# receiver.net
KiCad netlist of a schematic drawn in EAGLE
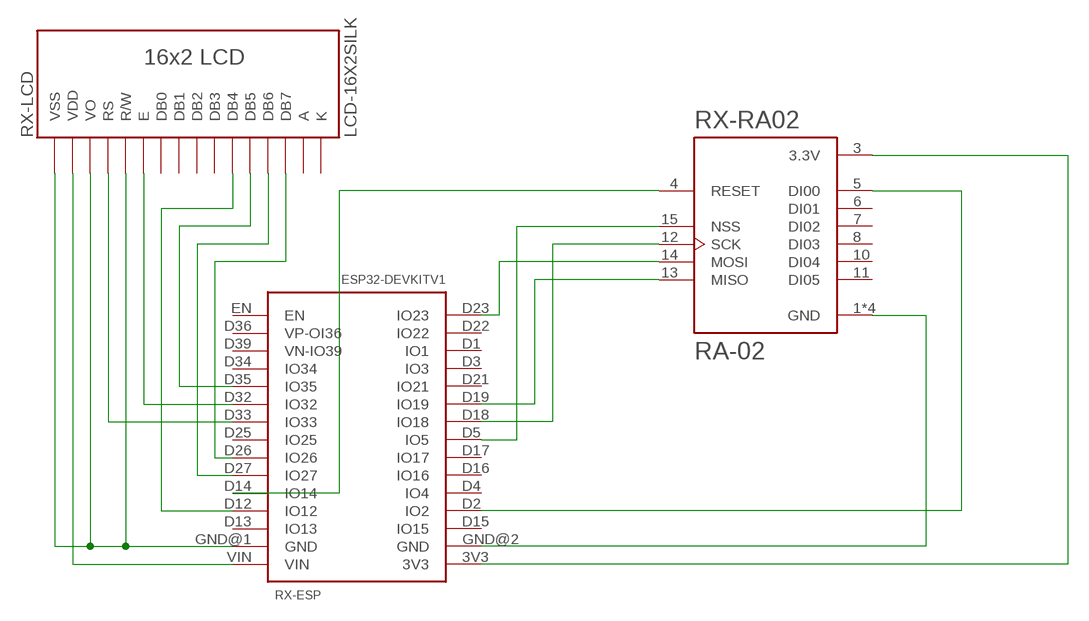
[diagram p0: schematic, sheet 1]

(export (version "E")
  (design (tool "Eeschema 10.0.6"))
  (components
    (comp (ref "RX-ESP")
      (value "ESP32DEVKITV1")
      (footprint "eagle-import:ESP32-DEVKITV1")
      (libsource (lib "eagle-import") (part "ESP32DEVKITV1"))
    )
    (comp (ref "RX-LCD")
      (value "LCD-16X2SILK")
      (footprint "eagle-import:MODULE_LCD-16X2")
      (fields (field (name "MF") "Gravitech") (field (name "MP") "LCD-16X2"))
      (libsource (lib "eagle-import") (part "LCD-16X2SILK"))
    )
    (comp (ref "RX-RA02")
      (value "RA-02")
      (footprint "eagle-import:RA-02")
      (fields (field (name "MF") "Ai-Thinker"))
      (libsource (lib "eagle-import") (part "RA-02"))
    )
  )
  (nets
    (net (code "1") (name "/A") (class "Default")
      (node (ref "RX-LCD") (pin "15") (pinfunction "A_15") (pintype "power_in"))
    )
    (net (code "2") (name "/K") (class "Default")
      (node (ref "RX-LCD") (pin "16") (pinfunction "K_16") (pintype "power_in"))
    )
    (net (code "3") (name "Net-(RX-ESP-GND-PadGND@2)") (class "Default")
      (node (ref "RX-ESP") (pin "GND@2") (pinfunction "GND_GND@2") (pintype "bidirectional"))
      (node (ref "RX-RA02") (pin "1") (pinfunction "GND_1") (pintype "power_in"))
      (node (ref "RX-RA02") (pin "16") (pinfunction "GND_16") (pintype "power_in"))
      (node (ref "RX-RA02") (pin "2") (pinfunction "GND_2") (pintype "power_in"))
      (node (ref "RX-RA02") (pin "9") (pinfunction "GND_9") (pintype "power_in"))
    )
    (net (code "4") (name "Net-(RX-ESP-IO2)") (class "Default")
      (node (ref "RX-ESP") (pin "D2") (pinfunction "IO2_D2") (pintype "bidirectional"))
      (node (ref "RX-RA02") (pin "5") (pinfunction "DI00_5") (pintype "bidirectional"))
    )
    (net (code "5") (name "Net-(RX-ESP-IO5)") (class "Default")
      (node (ref "RX-ESP") (pin "D5") (pinfunction "IO5_D5") (pintype "bidirectional"))
      (node (ref "RX-RA02") (pin "15") (pinfunction "NSS_15") (pintype "input"))
    )
    (net (code "6") (name "Net-(RX-ESP-IO12)") (class "Default")
      (node (ref "RX-ESP") (pin "D12") (pinfunction "IO12_D12") (pintype "bidirectional"))
      (node (ref "RX-LCD") (pin "11") (pinfunction "DB4_11") (pintype "bidirectional"))
    )
    (net (code "7") (name "Net-(RX-ESP-IO14)") (class "Default")
      (node (ref "RX-ESP") (pin "D14") (pinfunction "IO14_D14") (pintype "bidirectional"))
      (node (ref "RX-RA02") (pin "4") (pinfunction "RESET_4") (pintype "input"))
    )
    (net (code "8") (name "Net-(RX-ESP-IO18)") (class "Default")
      (node (ref "RX-ESP") (pin "D18") (pinfunction "IO18_D18") (pintype "bidirectional"))
      (node (ref "RX-RA02") (pin "12") (pinfunction "SCK_12") (pintype "input"))
    )
    (net (code "9") (name "Net-(RX-ESP-IO19)") (class "Default")
      (node (ref "RX-ESP") (pin "D19") (pinfunction "IO19_D19") (pintype "bidirectional"))
      (node (ref "RX-RA02") (pin "13") (pinfunction "MISO_13") (pintype "output"))
    )
    (net (code "10") (name "Net-(RX-ESP-IO23)") (class "Default")
      (node (ref "RX-ESP") (pin "D23") (pinfunction "IO23_D23") (pintype "bidirectional"))
      (node (ref "RX-RA02") (pin "14") (pinfunction "MOSI_14") (pintype "input"))
    )
    (net (code "11") (name "Net-(RX-ESP-IO26)") (class "Default")
      (node (ref "RX-ESP") (pin "D26") (pinfunction "IO26_D26") (pintype "bidirectional"))
      (node (ref "RX-LCD") (pin "14") (pinfunction "DB7_14") (pintype "bidirectional"))
    )
    (net (code "12") (name "Net-(RX-ESP-IO27)") (class "Default")
      (node (ref "RX-ESP") (pin "D27") (pinfunction "IO27_D27") (pintype "bidirectional"))
      (node (ref "RX-LCD") (pin "13") (pinfunction "DB6_13") (pintype "bidirectional"))
    )
    (net (code "13") (name "Net-(RX-ESP-IO32)") (class "Default")
      (node (ref "RX-ESP") (pin "D32") (pinfunction "IO32_D32") (pintype "bidirectional"))
      (node (ref "RX-LCD") (pin "6") (pinfunction "E_6") (pintype "input"))
    )
    (net (code "14") (name "Net-(RX-ESP-IO33)") (class "Default")
      (node (ref "RX-ESP") (pin "D33") (pinfunction "IO33_D33") (pintype "bidirectional"))
      (node (ref "RX-LCD") (pin "4") (pinfunction "RS_4") (pintype "input"))
    )
    (net (code "15") (name "Net-(RX-ESP-IO35)") (class "Default")
      (node (ref "RX-ESP") (pin "D35") (pinfunction "IO35_D35") (pintype "bidirectional"))
      (node (ref "RX-LCD") (pin "12") (pinfunction "DB5_12") (pintype "bidirectional"))
    )
    (net (code "16") (name "Net-(RX-LCD-R{slash}W)") (class "Default")
      (node (ref "RX-ESP") (pin "GND@1") (pinfunction "GND_GND@1") (pintype "bidirectional"))
      (node (ref "RX-LCD") (pin "1") (pinfunction "VSS_1") (pintype "power_in"))
      (node (ref "RX-LCD") (pin "3") (pinfunction "VO_3") (pintype "bidirectional"))
      (node (ref "RX-LCD") (pin "5") (pinfunction "R/W_5") (pintype "input"))
    )
    (net (code "17") (name "Net-(RX-LCD-VDD)") (class "Default")
      (node (ref "RX-ESP") (pin "VIN") (pinfunction "VIN_VIN") (pintype "bidirectional"))
      (node (ref "RX-LCD") (pin "2") (pinfunction "VDD_2") (pintype "power_in"))
    )
    (net (code "18") (name "Net-(RX-RA02-3.3V)") (class "Default")
      (node (ref "RX-ESP") (pin "3V3") (pinfunction "3V3_3V3") (pintype "bidirectional"))
      (node (ref "RX-RA02") (pin "3") (pinfunction "3.3V_3") (pintype "power_in"))
    )
    (net (code "19") (name "unconnected-(RX-ESP-IO1-PadD1)") (class "Default")
      (node (ref "RX-ESP") (pin "D1") (pinfunction "IO1_D1") (pintype "bidirectional"))
    )
    (net (code "20") (name "unconnected-(RX-ESP-IO3-PadD3)") (class "Default")
      (node (ref "RX-ESP") (pin "D3") (pinfunction "IO3_D3") (pintype "bidirectional"))
    )
    (net (code "21") (name "unconnected-(RX-ESP-IO4-PadD4)") (class "Default")
      (node (ref "RX-ESP") (pin "D4") (pinfunction "IO4_D4") (pintype "bidirectional"))
    )
    (net (code "22") (name "unconnected-(RX-ESP-IO13-PadD13)") (class "Default")
      (node (ref "RX-ESP") (pin "D13") (pinfunction "IO13_D13") (pintype "bidirectional"))
    )
    (net (code "23") (name "unconnected-(RX-ESP-IO15-PadD15)") (class "Default")
      (node (ref "RX-ESP") (pin "D15") (pinfunction "IO15_D15") (pintype "bidirectional"))
    )
    (net (code "24") (name "unconnected-(RX-ESP-IO16-PadD16)") (class "Default")
      (node (ref "RX-ESP") (pin "D16") (pinfunction "IO16_D16") (pintype "bidirectional"))
    )
    (net (code "25") (name "unconnected-(RX-ESP-IO17-PadD17)") (class "Default")
      (node (ref "RX-ESP") (pin "D17") (pinfunction "IO17_D17") (pintype "bidirectional"))
    )
    (net (code "26") (name "unconnected-(RX-ESP-IO21-PadD21)") (class "Default")
      (node (ref "RX-ESP") (pin "D21") (pinfunction "IO21_D21") (pintype "bidirectional"))
    )
    (net (code "27") (name "unconnected-(RX-ESP-IO22-PadD22)") (class "Default")
      (node (ref "RX-ESP") (pin "D22") (pinfunction "IO22_D22") (pintype "bidirectional"))
    )
    (net (code "28") (name "unconnected-(RX-ESP-IO25-PadD25)") (class "Default")
      (node (ref "RX-ESP") (pin "D25") (pinfunction "IO25_D25") (pintype "bidirectional"))
    )
    (net (code "29") (name "unconnected-(RX-ESP-IO34-PadD34)") (class "Default")
      (node (ref "RX-ESP") (pin "D34") (pinfunction "IO34_D34") (pintype "bidirectional"))
    )
    (net (code "30") (name "unconnected-(RX-ESP-PadEN)") (class "Default")
      (node (ref "RX-ESP") (pin "EN") (pinfunction "EN_EN") (pintype "bidirectional"))
    )
    (net (code "31") (name "unconnected-(RX-ESP-VN-IO39-PadD39)") (class "Default")
      (node (ref "RX-ESP") (pin "D39") (pinfunction "VN-IO39_D39") (pintype "bidirectional"))
    )
    (net (code "32") (name "unconnected-(RX-ESP-VP-OI36-PadD36)") (class "Default")
      (node (ref "RX-ESP") (pin "D36") (pinfunction "VP-OI36_D36") (pintype "bidirectional"))
    )
    (net (code "33") (name "unconnected-(RX-LCD-DB0-Pad7)") (class "Default")
      (node (ref "RX-LCD") (pin "7") (pinfunction "DB0_7") (pintype "bidirectional"))
    )
    (net (code "34") (name "unconnected-(RX-LCD-DB1-Pad8)") (class "Default")
      (node (ref "RX-LCD") (pin "8") (pinfunction "DB1_8") (pintype "bidirectional"))
    )
    (net (code "35") (name "unconnected-(RX-LCD-DB2-Pad9)") (class "Default")
      (node (ref "RX-LCD") (pin "9") (pinfunction "DB2_9") (pintype "bidirectional"))
    )
    (net (code "36") (name "unconnected-(RX-LCD-DB3-Pad10)") (class "Default")
      (node (ref "RX-LCD") (pin "10") (pinfunction "DB3_10") (pintype "bidirectional"))
    )
    (net (code "37") (name "unconnected-(RX-RA02-DI01-Pad6)") (class "Default")
      (node (ref "RX-RA02") (pin "6") (pinfunction "DI01_6") (pintype "bidirectional"))
    )
    (net (code "38") (name "unconnected-(RX-RA02-DI02-Pad7)") (class "Default")
      (node (ref "RX-RA02") (pin "7") (pinfunction "DI02_7") (pintype "bidirectional"))
    )
    (net (code "39") (name "unconnected-(RX-RA02-DI03-Pad8)") (class "Default")
      (node (ref "RX-RA02") (pin "8") (pinfunction "DI03_8") (pintype "bidirectional"))
    )
    (net (code "40") (name "unconnected-(RX-RA02-DI04-Pad10)") (class "Default")
      (node (ref "RX-RA02") (pin "10") (pinfunction "DI04_10") (pintype "bidirectional"))
    )
    (net (code "41") (name "unconnected-(RX-RA02-DI05-Pad11)") (class "Default")
      (node (ref "RX-RA02") (pin "11") (pinfunction "DI05_11") (pintype "bidirectional"))
    )
  )
)
